# VCAFront.net
KiCad netlist of a schematic drawn in EAGLE
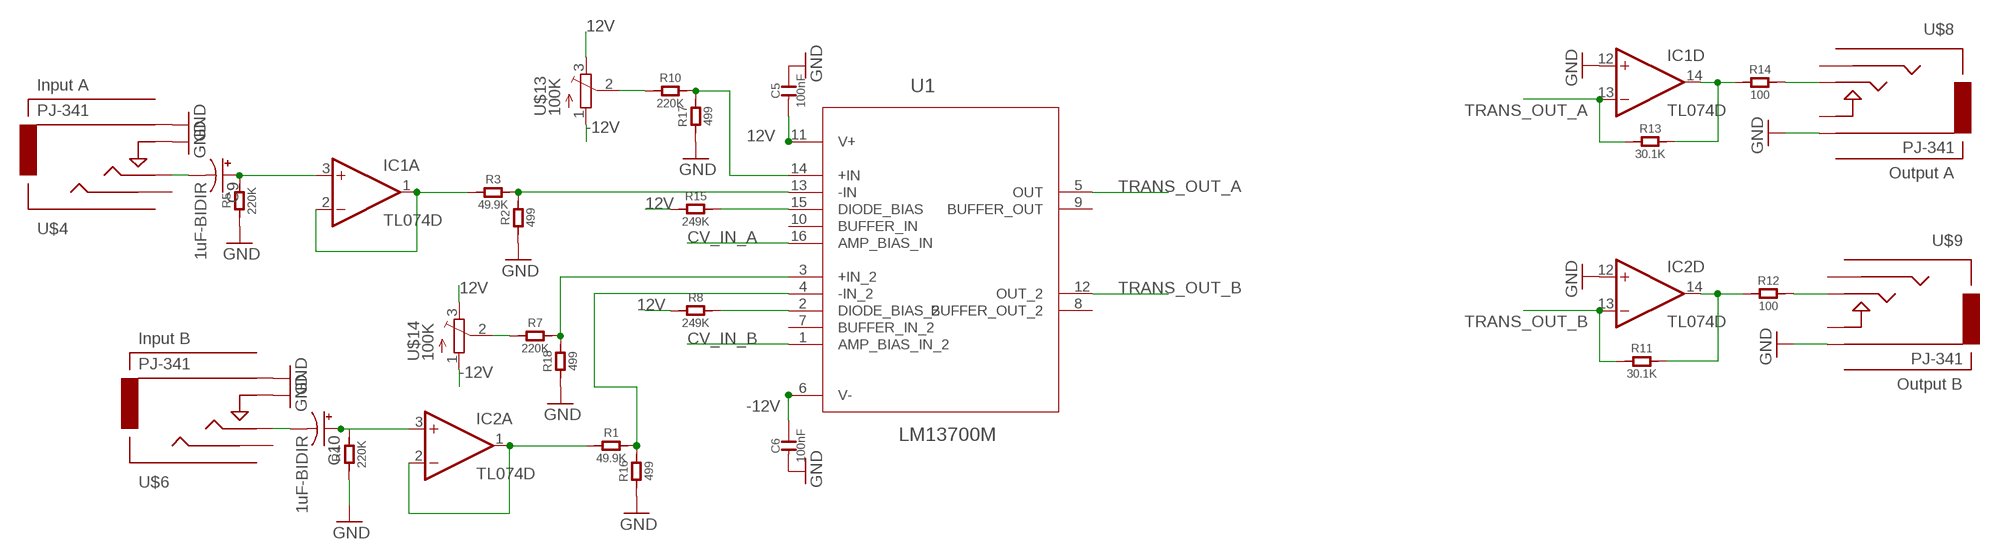
[diagram p0: schematic, sheet 1, part 1 of 2]
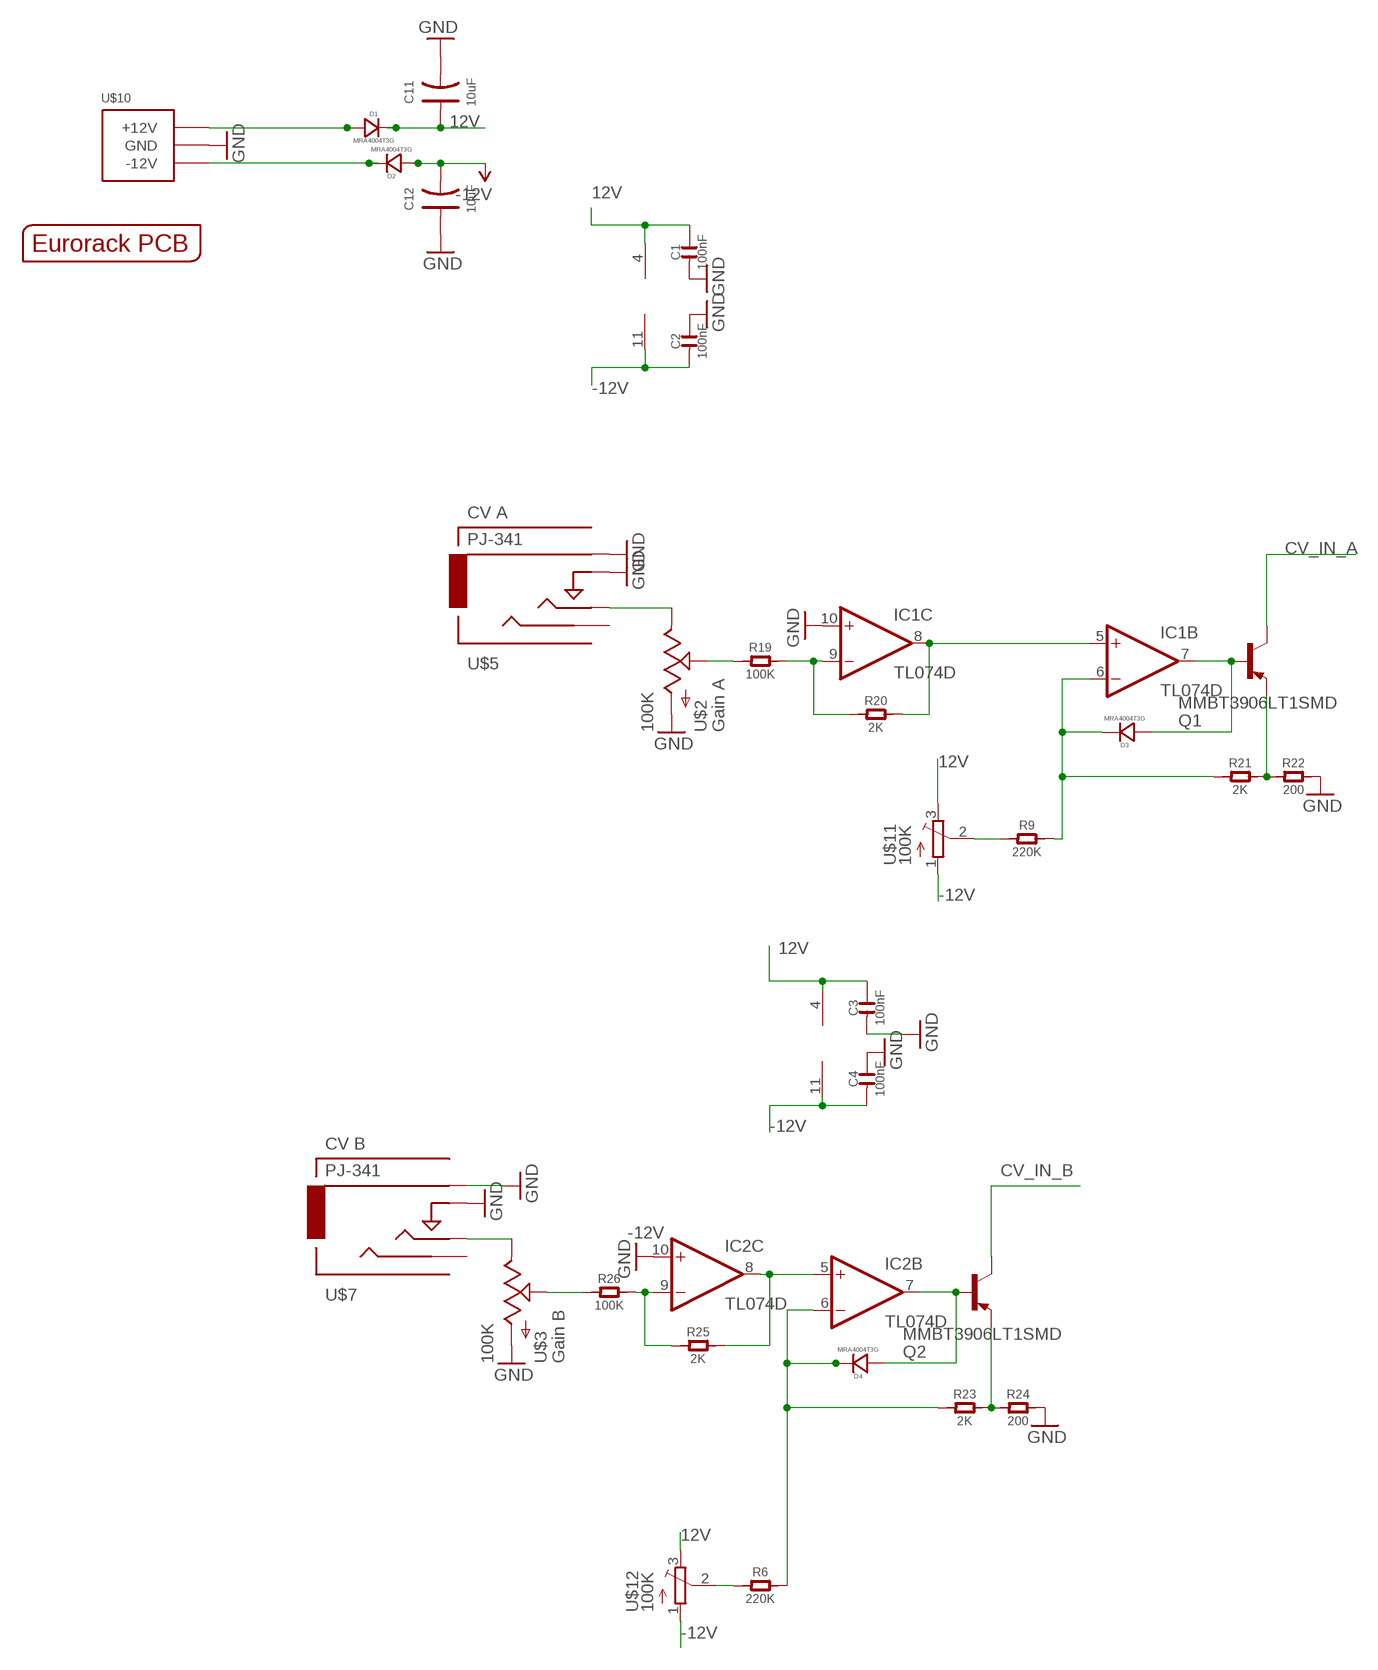
[diagram p1: schematic, sheet 1, part 2 of 2]

(export (version "E")
  (design (tool "Eeschema 10.0.6"))
  (components
    (comp (ref "C1")
      (value "100nF")
      (footprint "eagle-import:C0603")
      (libsource (lib "eagle-import") (part "C-0603"))
    )
    (comp (ref "C2")
      (value "100nF")
      (footprint "eagle-import:C0603")
      (libsource (lib "eagle-import") (part "C-0603"))
    )
    (comp (ref "C3")
      (value "100nF")
      (footprint "eagle-import:C0603")
      (libsource (lib "eagle-import") (part "C-0603"))
    )
    (comp (ref "C4")
      (value "100nF")
      (footprint "eagle-import:C0603")
      (libsource (lib "eagle-import") (part "C-0603"))
    )
    (comp (ref "C5")
      (value "100nF")
      (footprint "eagle-import:C0603")
      (libsource (lib "eagle-import") (part "C-0603"))
    )
    (comp (ref "C6")
      (value "100nF")
      (footprint "eagle-import:C0603")
      (libsource (lib "eagle-import") (part "C-0603"))
    )
    (comp (ref "C9")
      (value "1uF-BIDIR")
      (footprint "eagle-import:153CLV-0505")
      (libsource (lib "eagle-import") (part "CPOL-US153CLV-0505"))
    )
    (comp (ref "C10")
      (value "1uF-BIDIR")
      (footprint "eagle-import:153CLV-0505")
      (libsource (lib "eagle-import") (part "CPOL-US153CLV-0505"))
    )
    (comp (ref "C11")
      (value "10uF")
      (footprint "eagle-import:AVX-A")
      (libsource (lib "eagle-import") (part "C-POLAR-A"))
    )
    (comp (ref "C12")
      (value "10uF")
      (footprint "eagle-import:AVX-A")
      (libsource (lib "eagle-import") (part "C-POLAR-A"))
    )
    (comp (ref "D1")
      (value "MRA4004T3G")
      (footprint "eagle-import:DO-214AC")
      (fields (field (name "MF") "VISHAY") (field (name "MPN") "US1G-E3/5AT"))
      (libsource (lib "eagle-import") (part "D-SMA"))
    )
    (comp (ref "D2")
      (value "MRA4004T3G")
      (footprint "eagle-import:DO-214AC")
      (fields (field (name "MF") "VISHAY") (field (name "MPN") "US1G-E3/5AT"))
      (libsource (lib "eagle-import") (part "D-SMA"))
    )
    (comp (ref "D3")
      (value "MRA4004T3G")
      (footprint "eagle-import:DO-214AC")
      (fields (field (name "MF") "VISHAY") (field (name "MPN") "US1G-E3/5AT"))
      (libsource (lib "eagle-import") (part "D-SMA"))
    )
    (comp (ref "D4")
      (value "MRA4004T3G")
      (footprint "eagle-import:DO-214AC")
      (fields (field (name "MF") "VISHAY") (field (name "MPN") "US1G-E3/5AT"))
      (libsource (lib "eagle-import") (part "D-SMA"))
    )
    (comp (ref "IC1")
      (value "TL074D")
      (footprint "eagle-import:SO14")
      (libsource (lib "eagle-import") (part "TL074D"))
    )
    (comp (ref "IC2")
      (value "TL074D")
      (footprint "eagle-import:SO14")
      (libsource (lib "eagle-import") (part "TL074D"))
    )
    (comp (ref "Q1")
      (value "MMBT3906LT1SMD")
      (footprint "eagle-import:SOT23-BEC")
      (libsource (lib "eagle-import") (part "MMBT3906SMDLT1"))
    )
    (comp (ref "Q2")
      (value "MMBT3906LT1SMD")
      (footprint "eagle-import:SOT23-BEC")
      (libsource (lib "eagle-import") (part "MMBT3906SMDLT1"))
    )
    (comp (ref "R1")
      (value "49.9K")
      (footprint "eagle-import:C0805")
      (libsource (lib "eagle-import") (part "R"))
    )
    (comp (ref "R2")
      (value "499")
      (footprint "eagle-import:C0805")
      (libsource (lib "eagle-import") (part "R"))
    )
    (comp (ref "R3")
      (value "49.9K")
      (footprint "eagle-import:C0805")
      (libsource (lib "eagle-import") (part "R"))
    )
    (comp (ref "R4")
      (value "220K")
      (footprint "eagle-import:C0805")
      (libsource (lib "eagle-import") (part "R"))
    )
    (comp (ref "R5")
      (value "220K")
      (footprint "eagle-import:C0805")
      (libsource (lib "eagle-import") (part "R"))
    )
    (comp (ref "R6")
      (value "220K")
      (footprint "eagle-import:C0805")
      (libsource (lib "eagle-import") (part "R"))
    )
    (comp (ref "R7")
      (value "220K")
      (footprint "eagle-import:C0805")
      (libsource (lib "eagle-import") (part "R"))
    )
    (comp (ref "R8")
      (value "249K")
      (footprint "eagle-import:C0805")
      (libsource (lib "eagle-import") (part "R"))
    )
    (comp (ref "R9")
      (value "220K")
      (footprint "eagle-import:C0805")
      (libsource (lib "eagle-import") (part "R"))
    )
    (comp (ref "R10")
      (value "220K")
      (footprint "eagle-import:C0805")
      (libsource (lib "eagle-import") (part "R"))
    )
    (comp (ref "R11")
      (value "30.1K")
      (footprint "eagle-import:C0805")
      (libsource (lib "eagle-import") (part "R"))
    )
    (comp (ref "R12")
      (value "100")
      (footprint "eagle-import:C0805")
      (libsource (lib "eagle-import") (part "R"))
    )
    (comp (ref "R13")
      (value "30.1K")
      (footprint "eagle-import:C0805")
      (libsource (lib "eagle-import") (part "R"))
    )
    (comp (ref "R14")
      (value "100")
      (footprint "eagle-import:C0805")
      (libsource (lib "eagle-import") (part "R"))
    )
    (comp (ref "R15")
      (value "249K")
      (footprint "eagle-import:C0805")
      (libsource (lib "eagle-import") (part "R"))
    )
    (comp (ref "R16")
      (value "499")
      (footprint "eagle-import:C0805")
      (libsource (lib "eagle-import") (part "R"))
    )
    (comp (ref "R17")
      (value "499")
      (footprint "eagle-import:C0805")
      (libsource (lib "eagle-import") (part "R"))
    )
    (comp (ref "R18")
      (value "499")
      (footprint "eagle-import:C0805")
      (libsource (lib "eagle-import") (part "R"))
    )
    (comp (ref "R19")
      (value "100K")
      (footprint "eagle-import:C0805")
      (libsource (lib "eagle-import") (part "R"))
    )
    (comp (ref "R20")
      (value "2K")
      (footprint "eagle-import:C0805")
      (libsource (lib "eagle-import") (part "R"))
    )
    (comp (ref "R21")
      (value "2K")
      (footprint "eagle-import:C0805")
      (libsource (lib "eagle-import") (part "R"))
    )
    (comp (ref "R22")
      (value "200")
      (footprint "eagle-import:C0805")
      (libsource (lib "eagle-import") (part "R"))
    )
    (comp (ref "R23")
      (value "2K")
      (footprint "eagle-import:C0805")
      (libsource (lib "eagle-import") (part "R"))
    )
    (comp (ref "R24")
      (value "200")
      (footprint "eagle-import:C0805")
      (libsource (lib "eagle-import") (part "R"))
    )
    (comp (ref "R25")
      (value "2K")
      (footprint "eagle-import:C0805")
      (libsource (lib "eagle-import") (part "R"))
    )
    (comp (ref "R26")
      (value "100K")
      (footprint "eagle-import:C0805")
      (libsource (lib "eagle-import") (part "R"))
    )
    (comp (ref "U$1")
      (value "EURORACK_PCB4HP")
      (footprint "eagle-import:EURORACK4HPPCB")
      (libsource (lib "eagle-import") (part "EURORACK_PCB4HP"))
    )
    (comp (ref "U$2")
      (value "100K")
      (footprint "eagle-import:OG-POTS_ALPS_POT_VERTICAL")
      (fields (field (name "DESC") "Gain A"))
      (libsource (lib "eagle-import") (part "POTZEPHPOT"))
    )
    (comp (ref "U$3")
      (value "100K")
      (footprint "eagle-import:OG-POTS_ALPS_POT_VERTICAL")
      (fields (field (name "DESC") "Gain B"))
      (libsource (lib "eagle-import") (part "POTZEPHPOT"))
    )
    (comp (ref "U$4")
      (value "PJ-341")
      (footprint "eagle-import:3.5MM-JACK-SWITCH-13MM-INPUT")
      (fields (field (name "DESC") "Input A"))
      (libsource (lib "eagle-import") (part "AUDIO-JACKINPUT"))
    )
    (comp (ref "U$5")
      (value "PJ-341")
      (footprint "eagle-import:3.5MM-JACK-SWITCH-13MM-INPUT")
      (fields (field (name "DESC") "CV A"))
      (libsource (lib "eagle-import") (part "AUDIO-JACKINPUT"))
    )
    (comp (ref "U$6")
      (value "PJ-341")
      (footprint "eagle-import:3.5MM-JACK-SWITCH-13MM-INPUT")
      (fields (field (name "DESC") "Input B"))
      (libsource (lib "eagle-import") (part "AUDIO-JACKINPUT"))
    )
    (comp (ref "U$7")
      (value "PJ-341")
      (footprint "eagle-import:3.5MM-JACK-SWITCH-13MM-INPUT")
      (fields (field (name "DESC") "CV B"))
      (libsource (lib "eagle-import") (part "AUDIO-JACKINPUT"))
    )
    (comp (ref "U$8")
      (value "PJ-341")
      (footprint "eagle-import:3.5MM-JACK-SWITCH-13MM-OUTPUT")
      (fields (field (name "DESC") "Output A"))
      (libsource (lib "eagle-import") (part "AUDIO-JACKOUTPUT"))
    )
    (comp (ref "U$9")
      (value "PJ-341")
      (footprint "eagle-import:3.5MM-JACK-SWITCH-13MM-OUTPUT")
      (fields (field (name "DESC") "Output B"))
      (libsource (lib "eagle-import") (part "AUDIO-JACKOUTPUT"))
    )
    (comp (ref "U$10")
      (value "POWER_SIMPLE10")
      (footprint "eagle-import:POWER_10")
      (libsource (lib "eagle-import") (part "POWER_SIMPLE10"))
    )
    (comp (ref "U$11")
      (value "100K")
      (footprint "eagle-import:TC33X")
      (libsource (lib "eagle-import") (part "TRIMPOTTC33X"))
    )
    (comp (ref "U$12")
      (value "100K")
      (footprint "eagle-import:TC33X")
      (libsource (lib "eagle-import") (part "TRIMPOTTC33X"))
    )
    (comp (ref "U$13")
      (value "100K")
      (footprint "eagle-import:TC33X")
      (libsource (lib "eagle-import") (part "TRIMPOTTC33X"))
    )
    (comp (ref "U$14")
      (value "100K")
      (footprint "eagle-import:TC33X")
      (libsource (lib "eagle-import") (part "TRIMPOTTC33X"))
    )
    (comp (ref "U1")
      (value "LM13700M")
      (footprint "eagle-import:SOIC127P620X175-16N")
      (libsource (lib "eagle-import") (part "LM13700M"))
    )
  )
  (nets
    (net (code "1") (name "-12V") (class "Default")
      (node (ref "C12") (pin "-") (pinfunction "2_-") (pintype "bidirectional"))
      (node (ref "C2") (pin "1") (pinfunction "1_1") (pintype "bidirectional"))
      (node (ref "C4") (pin "1") (pinfunction "1_1") (pintype "bidirectional"))
      (node (ref "C6") (pin "2") (pinfunction "2_2") (pintype "bidirectional"))
      (node (ref "D2") (pin "1") (pinfunction "+_1") (pintype "passive"))
      (node (ref "IC1") (pin "11") (pinfunction "V-_11") (pintype "power_in"))
      (node (ref "IC2") (pin "11") (pinfunction "V-_11") (pintype "power_in"))
      (node (ref "U$11") (pin "1") (pinfunction "A_1") (pintype "passive"))
      (node (ref "U$12") (pin "1") (pinfunction "A_1") (pintype "passive"))
      (node (ref "U$13") (pin "1") (pinfunction "A_1") (pintype "passive"))
      (node (ref "U$14") (pin "1") (pinfunction "A_1") (pintype "passive"))
      (node (ref "U1") (pin "6") (pinfunction "V-_6") (pintype "power_in"))
    )
    (net (code "2") (name "/12V") (class "Default")
      (node (ref "C1") (pin "2") (pinfunction "2_2") (pintype "bidirectional"))
      (node (ref "C11") (pin "+") (pinfunction "1_+") (pintype "bidirectional"))
      (node (ref "C3") (pin "2") (pinfunction "2_2") (pintype "bidirectional"))
      (node (ref "C5") (pin "1") (pinfunction "1_1") (pintype "bidirectional"))
      (node (ref "D1") (pin "2") (pinfunction "-_2") (pintype "passive"))
      (node (ref "IC1") (pin "4") (pinfunction "V+_4") (pintype "power_in"))
      (node (ref "IC2") (pin "4") (pinfunction "V+_4") (pintype "power_in"))
      (node (ref "R15") (pin "1") (pinfunction "1_1") (pintype "bidirectional"))
      (node (ref "R8") (pin "1") (pinfunction "1_1") (pintype "bidirectional"))
      (node (ref "U$11") (pin "3") (pinfunction "E_3") (pintype "passive"))
      (node (ref "U$12") (pin "3") (pinfunction "E_3") (pintype "passive"))
      (node (ref "U$13") (pin "3") (pinfunction "E_3") (pintype "passive"))
      (node (ref "U$14") (pin "3") (pinfunction "E_3") (pintype "passive"))
      (node (ref "U1") (pin "11") (pinfunction "V+_11") (pintype "power_in"))
    )
    (net (code "3") (name "/CV_IN_A") (class "Default")
      (node (ref "Q1") (pin "C") (pinfunction "C_C") (pintype "passive"))
      (node (ref "U1") (pin "16") (pinfunction "AMP_BIAS_IN_16") (pintype "input"))
    )
    (net (code "4") (name "/CV_IN_B") (class "Default")
      (node (ref "Q2") (pin "C") (pinfunction "C_C") (pintype "passive"))
      (node (ref "U1") (pin "1") (pinfunction "AMP_BIAS_IN_2_1") (pintype "input"))
    )
    (net (code "5") (name "/TRANS_OUT_A") (class "Default")
      (node (ref "IC1") (pin "13") (pinfunction "-IN_13") (pintype "input"))
      (node (ref "R13") (pin "1") (pinfunction "1_1") (pintype "bidirectional"))
      (node (ref "U1") (pin "5") (pinfunction "OUT_5") (pintype "output"))
    )
    (net (code "6") (name "/TRANS_OUT_B") (class "Default")
      (node (ref "IC2") (pin "13") (pinfunction "-IN_13") (pintype "input"))
      (node (ref "R11") (pin "1") (pinfunction "1_1") (pintype "bidirectional"))
      (node (ref "U1") (pin "12") (pinfunction "OUT_2_12") (pintype "output"))
    )
    (net (code "7") (name "GND") (class "Default")
      (node (ref "C1") (pin "1") (pinfunction "1_1") (pintype "bidirectional"))
      (node (ref "C11") (pin "-") (pinfunction "2_-") (pintype "bidirectional"))
      (node (ref "C12") (pin "+") (pinfunction "1_+") (pintype "bidirectional"))
      (node (ref "C2") (pin "2") (pinfunction "2_2") (pintype "bidirectional"))
      (node (ref "C3") (pin "1") (pinfunction "1_1") (pintype "bidirectional"))
      (node (ref "C4") (pin "2") (pinfunction "2_2") (pintype "bidirectional"))
      (node (ref "C5") (pin "2") (pinfunction "2_2") (pintype "bidirectional"))
      (node (ref "C6") (pin "1") (pinfunction "1_1") (pintype "bidirectional"))
      (node (ref "IC1") (pin "10") (pinfunction "+IN_10") (pintype "input"))
      (node (ref "IC1") (pin "12") (pinfunction "+IN_12") (pintype "input"))
      (node (ref "IC2") (pin "10") (pinfunction "+IN_10") (pintype "input"))
      (node (ref "IC2") (pin "12") (pinfunction "+IN_12") (pintype "input"))
      (node (ref "R16") (pin "1") (pinfunction "1_1") (pintype "bidirectional"))
      (node (ref "R17") (pin "1") (pinfunction "1_1") (pintype "bidirectional"))
      (node (ref "R18") (pin "1") (pinfunction "1_1") (pintype "bidirectional"))
      (node (ref "R2") (pin "1") (pinfunction "1_1") (pintype "bidirectional"))
      (node (ref "R22") (pin "2") (pinfunction "2_2") (pintype "bidirectional"))
      (node (ref "R24") (pin "2") (pinfunction "2_2") (pintype "bidirectional"))
      (node (ref "R4") (pin "1") (pinfunction "1_1") (pintype "bidirectional"))
      (node (ref "R5") (pin "1") (pinfunction "1_1") (pintype "bidirectional"))
      (node (ref "U$10") (pin "3") (pinfunction "GND_3") (pintype "bidirectional"))
      (node (ref "U$10") (pin "4") (pinfunction "GND_4") (pintype "bidirectional"))
      (node (ref "U$10") (pin "5") (pinfunction "GND_5") (pintype "bidirectional"))
      (node (ref "U$10") (pin "6") (pinfunction "GND_6") (pintype "bidirectional"))
      (node (ref "U$10") (pin "7") (pinfunction "GND_7") (pintype "bidirectional"))
      (node (ref "U$10") (pin "8") (pinfunction "GND_8") (pintype "bidirectional"))
      (node (ref "U$2") (pin "P$3") (pinfunction "A_P$3") (pintype "passive"))
      (node (ref "U$3") (pin "P$3") (pinfunction "A_P$3") (pintype "passive"))
      (node (ref "U$4") (pin "RING@3") (pinfunction "RING_RING@3") (pintype "bidirectional"))
      (node (ref "U$4") (pin "SWITCH@3") (pinfunction "SWITCH_SWITCH@3") (pintype "bidirectional"))
      (node (ref "U$5") (pin "RING@3") (pinfunction "RING_RING@3") (pintype "bidirectional"))
      (node (ref "U$5") (pin "SWITCH@3") (pinfunction "SWITCH_SWITCH@3") (pintype "bidirectional"))
      (node (ref "U$6") (pin "RING@3") (pinfunction "RING_RING@3") (pintype "bidirectional"))
      (node (ref "U$6") (pin "SWITCH@3") (pinfunction "SWITCH_SWITCH@3") (pintype "bidirectional"))
      (node (ref "U$7") (pin "RING@3") (pinfunction "RING_RING@3") (pintype "bidirectional"))
      (node (ref "U$7") (pin "SWITCH@3") (pinfunction "SWITCH_SWITCH@3") (pintype "bidirectional"))
      (node (ref "U$8") (pin "RING@3") (pinfunction "RING_RING@3") (pintype "bidirectional"))
      (node (ref "U$9") (pin "RING@3") (pinfunction "RING_RING@3") (pintype "bidirectional"))
    )
    (net (code "8") (name "Net-(D1-+)") (class "Default")
      (node (ref "D1") (pin "1") (pinfunction "+_1") (pintype "passive"))
      (node (ref "U$10") (pin "10") (pinfunction "+12V_10") (pintype "bidirectional"))
      (node (ref "U$10") (pin "9") (pinfunction "+12V_9") (pintype "bidirectional"))
    )
    (net (code "9") (name "Net-(D2--)") (class "Default")
      (node (ref "D2") (pin "2") (pinfunction "-_2") (pintype "passive"))
      (node (ref "U$10") (pin "1") (pinfunction "-12V_1") (pintype "bidirectional"))
      (node (ref "U$10") (pin "2") (pinfunction "-12V_2") (pintype "bidirectional"))
    )
    (net (code "10") (name "Net-(D3-+)") (class "Default")
      (node (ref "D3") (pin "1") (pinfunction "+_1") (pintype "passive"))
      (node (ref "IC1") (pin "7") (pinfunction "OUT_7") (pintype "output"))
      (node (ref "Q1") (pin "B") (pinfunction "B_B") (pintype "passive"))
    )
    (net (code "11") (name "Net-(D3--)") (class "Default")
      (node (ref "D3") (pin "2") (pinfunction "-_2") (pintype "passive"))
      (node (ref "IC1") (pin "6") (pinfunction "-IN_6") (pintype "input"))
      (node (ref "R21") (pin "1") (pinfunction "1_1") (pintype "bidirectional"))
      (node (ref "R9") (pin "2") (pinfunction "2_2") (pintype "bidirectional"))
    )
    (net (code "12") (name "Net-(D4-+)") (class "Default")
      (node (ref "D4") (pin "1") (pinfunction "+_1") (pintype "passive"))
      (node (ref "IC2") (pin "7") (pinfunction "OUT_7") (pintype "output"))
      (node (ref "Q2") (pin "B") (pinfunction "B_B") (pintype "passive"))
    )
    (net (code "13") (name "Net-(D4--)") (class "Default")
      (node (ref "D4") (pin "2") (pinfunction "-_2") (pintype "passive"))
      (node (ref "IC2") (pin "6") (pinfunction "-IN_6") (pintype "input"))
      (node (ref "R23") (pin "1") (pinfunction "1_1") (pintype "bidirectional"))
      (node (ref "R6") (pin "2") (pinfunction "2_2") (pintype "bidirectional"))
    )
    (net (code "14") (name "Net-(IC1A-+IN)") (class "Default")
      (node (ref "C9") (pin "+") (pinfunction "+_+") (pintype "passive"))
      (node (ref "IC1") (pin "3") (pinfunction "+IN_3") (pintype "input"))
      (node (ref "R5") (pin "2") (pinfunction "2_2") (pintype "bidirectional"))
    )
    (net (code "15") (name "Net-(IC1A--IN)") (class "Default")
      (node (ref "IC1") (pin "1") (pinfunction "OUT_1") (pintype "output"))
      (node (ref "IC1") (pin "2") (pinfunction "-IN_2") (pintype "input"))
      (node (ref "R3") (pin "1") (pinfunction "1_1") (pintype "bidirectional"))
    )
    (net (code "16") (name "Net-(IC1B-+IN)") (class "Default")
      (node (ref "IC1") (pin "5") (pinfunction "+IN_5") (pintype "input"))
      (node (ref "IC1") (pin "8") (pinfunction "OUT_8") (pintype "output"))
      (node (ref "R20") (pin "2") (pinfunction "2_2") (pintype "bidirectional"))
    )
    (net (code "17") (name "Net-(IC1C--IN)") (class "Default")
      (node (ref "IC1") (pin "9") (pinfunction "-IN_9") (pintype "input"))
      (node (ref "R19") (pin "2") (pinfunction "2_2") (pintype "bidirectional"))
      (node (ref "R20") (pin "1") (pinfunction "1_1") (pintype "bidirectional"))
    )
    (net (code "18") (name "Net-(IC1D-OUT)") (class "Default")
      (node (ref "IC1") (pin "14") (pinfunction "OUT_14") (pintype "output"))
      (node (ref "R13") (pin "2") (pinfunction "2_2") (pintype "bidirectional"))
      (node (ref "R14") (pin "1") (pinfunction "1_1") (pintype "bidirectional"))
    )
    (net (code "19") (name "Net-(IC2A-+IN)") (class "Default")
      (node (ref "C10") (pin "+") (pinfunction "+_+") (pintype "passive"))
      (node (ref "IC2") (pin "3") (pinfunction "+IN_3") (pintype "input"))
      (node (ref "R4") (pin "2") (pinfunction "2_2") (pintype "bidirectional"))
    )
    (net (code "20") (name "Net-(IC2A--IN)") (class "Default")
      (node (ref "IC2") (pin "1") (pinfunction "OUT_1") (pintype "output"))
      (node (ref "IC2") (pin "2") (pinfunction "-IN_2") (pintype "input"))
      (node (ref "R1") (pin "1") (pinfunction "1_1") (pintype "bidirectional"))
    )
    (net (code "21") (name "Net-(IC2B-+IN)") (class "Default")
      (node (ref "IC2") (pin "5") (pinfunction "+IN_5") (pintype "input"))
      (node (ref "IC2") (pin "8") (pinfunction "OUT_8") (pintype "output"))
      (node (ref "R25") (pin "2") (pinfunction "2_2") (pintype "bidirectional"))
    )
    (net (code "22") (name "Net-(IC2C--IN)") (class "Default")
      (node (ref "IC2") (pin "9") (pinfunction "-IN_9") (pintype "input"))
      (node (ref "R25") (pin "1") (pinfunction "1_1") (pintype "bidirectional"))
      (node (ref "R26") (pin "2") (pinfunction "2_2") (pintype "bidirectional"))
    )
    (net (code "23") (name "Net-(IC2D-OUT)") (class "Default")
      (node (ref "IC2") (pin "14") (pinfunction "OUT_14") (pintype "output"))
      (node (ref "R11") (pin "2") (pinfunction "2_2") (pintype "bidirectional"))
      (node (ref "R12") (pin "1") (pinfunction "1_1") (pintype "bidirectional"))
    )
    (net (code "24") (name "Net-(Q1-PadE)") (class "Default")
      (node (ref "Q1") (pin "E") (pinfunction "E_E") (pintype "passive"))
      (node (ref "R21") (pin "2") (pinfunction "2_2") (pintype "bidirectional"))
      (node (ref "R22") (pin "1") (pinfunction "1_1") (pintype "bidirectional"))
    )
    (net (code "25") (name "Net-(Q2-PadE)") (class "Default")
      (node (ref "Q2") (pin "E") (pinfunction "E_E") (pintype "passive"))
      (node (ref "R23") (pin "2") (pinfunction "2_2") (pintype "bidirectional"))
      (node (ref "R24") (pin "1") (pinfunction "1_1") (pintype "bidirectional"))
    )
    (net (code "26") (name "Net-(U$2-E)") (class "Default")
      (node (ref "U$2") (pin "P$1") (pinfunction "E_P$1") (pintype "passive"))
      (node (ref "U$5") (pin "TIP@3") (pinfunction "TIP_TIP@3") (pintype "bidirectional"))
    )
    (net (code "27") (name "Net-(U$2-S)") (class "Default")
      (node (ref "R19") (pin "1") (pinfunction "1_1") (pintype "bidirectional"))
      (node (ref "U$2") (pin "P$2") (pinfunction "S_P$2") (pintype "passive"))
    )
    (net (code "28") (name "Net-(U$3-E)") (class "Default")
      (node (ref "U$3") (pin "P$1") (pinfunction "E_P$1") (pintype "passive"))
      (node (ref "U$7") (pin "TIP@3") (pinfunction "TIP_TIP@3") (pintype "bidirectional"))
    )
    (net (code "29") (name "Net-(U$3-S)") (class "Default")
      (node (ref "R26") (pin "1") (pinfunction "1_1") (pintype "bidirectional"))
      (node (ref "U$3") (pin "P$2") (pinfunction "S_P$2") (pintype "passive"))
    )
    (net (code "30") (name "Net-(U$4-TIP)") (class "Default")
      (node (ref "C9") (pin "-") (pinfunction "-_-") (pintype "passive"))
      (node (ref "U$4") (pin "TIP@3") (pinfunction "TIP_TIP@3") (pintype "bidirectional"))
    )
    (net (code "31") (name "Net-(U$6-TIP)") (class "Default")
      (node (ref "C10") (pin "-") (pinfunction "-_-") (pintype "passive"))
      (node (ref "U$6") (pin "TIP@3") (pinfunction "TIP_TIP@3") (pintype "bidirectional"))
    )
    (net (code "32") (name "Net-(U$8-TIP)") (class "Default")
      (node (ref "R14") (pin "2") (pinfunction "2_2") (pintype "bidirectional"))
      (node (ref "U$8") (pin "TIP@3") (pinfunction "TIP_TIP@3") (pintype "bidirectional"))
    )
    (net (code "33") (name "Net-(U$9-TIP)") (class "Default")
      (node (ref "R12") (pin "2") (pinfunction "2_2") (pintype "bidirectional"))
      (node (ref "U$9") (pin "TIP@3") (pinfunction "TIP_TIP@3") (pintype "bidirectional"))
    )
    (net (code "34") (name "Net-(U$11-S)") (class "Default")
      (node (ref "R9") (pin "1") (pinfunction "1_1") (pintype "bidirectional"))
      (node (ref "U$11") (pin "2") (pinfunction "S_2") (pintype "passive"))
    )
    (net (code "35") (name "Net-(U$12-S)") (class "Default")
      (node (ref "R6") (pin "1") (pinfunction "1_1") (pintype "bidirectional"))
      (node (ref "U$12") (pin "2") (pinfunction "S_2") (pintype "passive"))
    )
    (net (code "36") (name "Net-(U$13-S)") (class "Default")
      (node (ref "R10") (pin "1") (pinfunction "1_1") (pintype "bidirectional"))
      (node (ref "U$13") (pin "2") (pinfunction "S_2") (pintype "passive"))
    )
    (net (code "37") (name "Net-(U$14-S)") (class "Default")
      (node (ref "R7") (pin "1") (pinfunction "1_1") (pintype "bidirectional"))
      (node (ref "U$14") (pin "2") (pinfunction "S_2") (pintype "passive"))
    )
    (net (code "38") (name "Net-(U1-+IN)") (class "Default")
      (node (ref "R10") (pin "2") (pinfunction "2_2") (pintype "bidirectional"))
      (node (ref "R17") (pin "2") (pinfunction "2_2") (pintype "bidirectional"))
      (node (ref "U1") (pin "14") (pinfunction "+IN_14") (pintype "input"))
    )
    (net (code "39") (name "Net-(U1-+IN_2)") (class "Default")
      (node (ref "R18") (pin "2") (pinfunction "2_2") (pintype "bidirectional"))
      (node (ref "R7") (pin "2") (pinfunction "2_2") (pintype "bidirectional"))
      (node (ref "U1") (pin "3") (pinfunction "+IN_2_3") (pintype "input"))
    )
    (net (code "40") (name "Net-(U1--IN)") (class "Default")
      (node (ref "R2") (pin "2") (pinfunction "2_2") (pintype "bidirectional"))
      (node (ref "R3") (pin "2") (pinfunction "2_2") (pintype "bidirectional"))
      (node (ref "U1") (pin "13") (pinfunction "-IN_13") (pintype "input"))
    )
    (net (code "41") (name "Net-(U1--IN_2)") (class "Default")
      (node (ref "R1") (pin "2") (pinfunction "2_2") (pintype "bidirectional"))
      (node (ref "R16") (pin "2") (pinfunction "2_2") (pintype "bidirectional"))
      (node (ref "U1") (pin "4") (pinfunction "-IN_2_4") (pintype "input"))
    )
    (net (code "42") (name "Net-(U1-DIODE_BIAS)") (class "Default")
      (node (ref "R15") (pin "2") (pinfunction "2_2") (pintype "bidirectional"))
      (node (ref "U1") (pin "15") (pinfunction "DIODE_BIAS_15") (pintype "input"))
    )
    (net (code "43") (name "Net-(U1-DIODE_BIAS_2)") (class "Default")
      (node (ref "R8") (pin "2") (pinfunction "2_2") (pintype "bidirectional"))
      (node (ref "U1") (pin "2") (pinfunction "DIODE_BIAS_2_2") (pintype "input"))
    )
    (net (code "44") (name "unconnected-(U$4-SECOND-PadSECOND@3)") (class "Default")
      (node (ref "U$4") (pin "SECOND@3") (pinfunction "SECOND_SECOND@3") (pintype "bidirectional"))
    )
    (net (code "45") (name "unconnected-(U$5-SECOND-PadSECOND@3)") (class "Default")
      (node (ref "U$5") (pin "SECOND@3") (pinfunction "SECOND_SECOND@3") (pintype "bidirectional"))
    )
    (net (code "46") (name "unconnected-(U$6-SECOND-PadSECOND@3)") (class "Default")
      (node (ref "U$6") (pin "SECOND@3") (pinfunction "SECOND_SECOND@3") (pintype "bidirectional"))
    )
    (net (code "47") (name "unconnected-(U$7-SECOND-PadSECOND@3)") (class "Default")
      (node (ref "U$7") (pin "SECOND@3") (pinfunction "SECOND_SECOND@3") (pintype "bidirectional"))
    )
    (net (code "48") (name "unconnected-(U$8-SECOND-PadSECOND@3)") (class "Default")
      (node (ref "U$8") (pin "SECOND@3") (pinfunction "SECOND_SECOND@3") (pintype "bidirectional"))
    )
    (net (code "49") (name "unconnected-(U$8-SWITCH-PadSWITCH@3)") (class "Default")
      (node (ref "U$8") (pin "SWITCH@3") (pinfunction "SWITCH_SWITCH@3") (pintype "bidirectional"))
    )
    (net (code "50") (name "unconnected-(U$9-SECOND-PadSECOND@3)") (class "Default")
      (node (ref "U$9") (pin "SECOND@3") (pinfunction "SECOND_SECOND@3") (pintype "bidirectional"))
    )
    (net (code "51") (name "unconnected-(U$9-SWITCH-PadSWITCH@3)") (class "Default")
      (node (ref "U$9") (pin "SWITCH@3") (pinfunction "SWITCH_SWITCH@3") (pintype "bidirectional"))
    )
    (net (code "52") (name "unconnected-(U1-BUFFER_IN-Pad10)") (class "Default")
      (node (ref "U1") (pin "10") (pinfunction "BUFFER_IN_10") (pintype "input"))
    )
    (net (code "53") (name "unconnected-(U1-BUFFER_IN_2-Pad7)") (class "Default")
      (node (ref "U1") (pin "7") (pinfunction "BUFFER_IN_2_7") (pintype "input"))
    )
    (net (code "54") (name "unconnected-(U1-BUFFER_OUT-Pad9)") (class "Default")
      (node (ref "U1") (pin "9") (pinfunction "BUFFER_OUT_9") (pintype "output"))
    )
    (net (code "55") (name "unconnected-(U1-BUFFER_OUT_2-Pad8)") (class "Default")
      (node (ref "U1") (pin "8") (pinfunction "BUFFER_OUT_2_8") (pintype "output"))
    )
  )
)
